# ProPrj_PocketEPD_2025-11-28.net
KiCad netlist of a schematic drawn in EasyEDA Pro
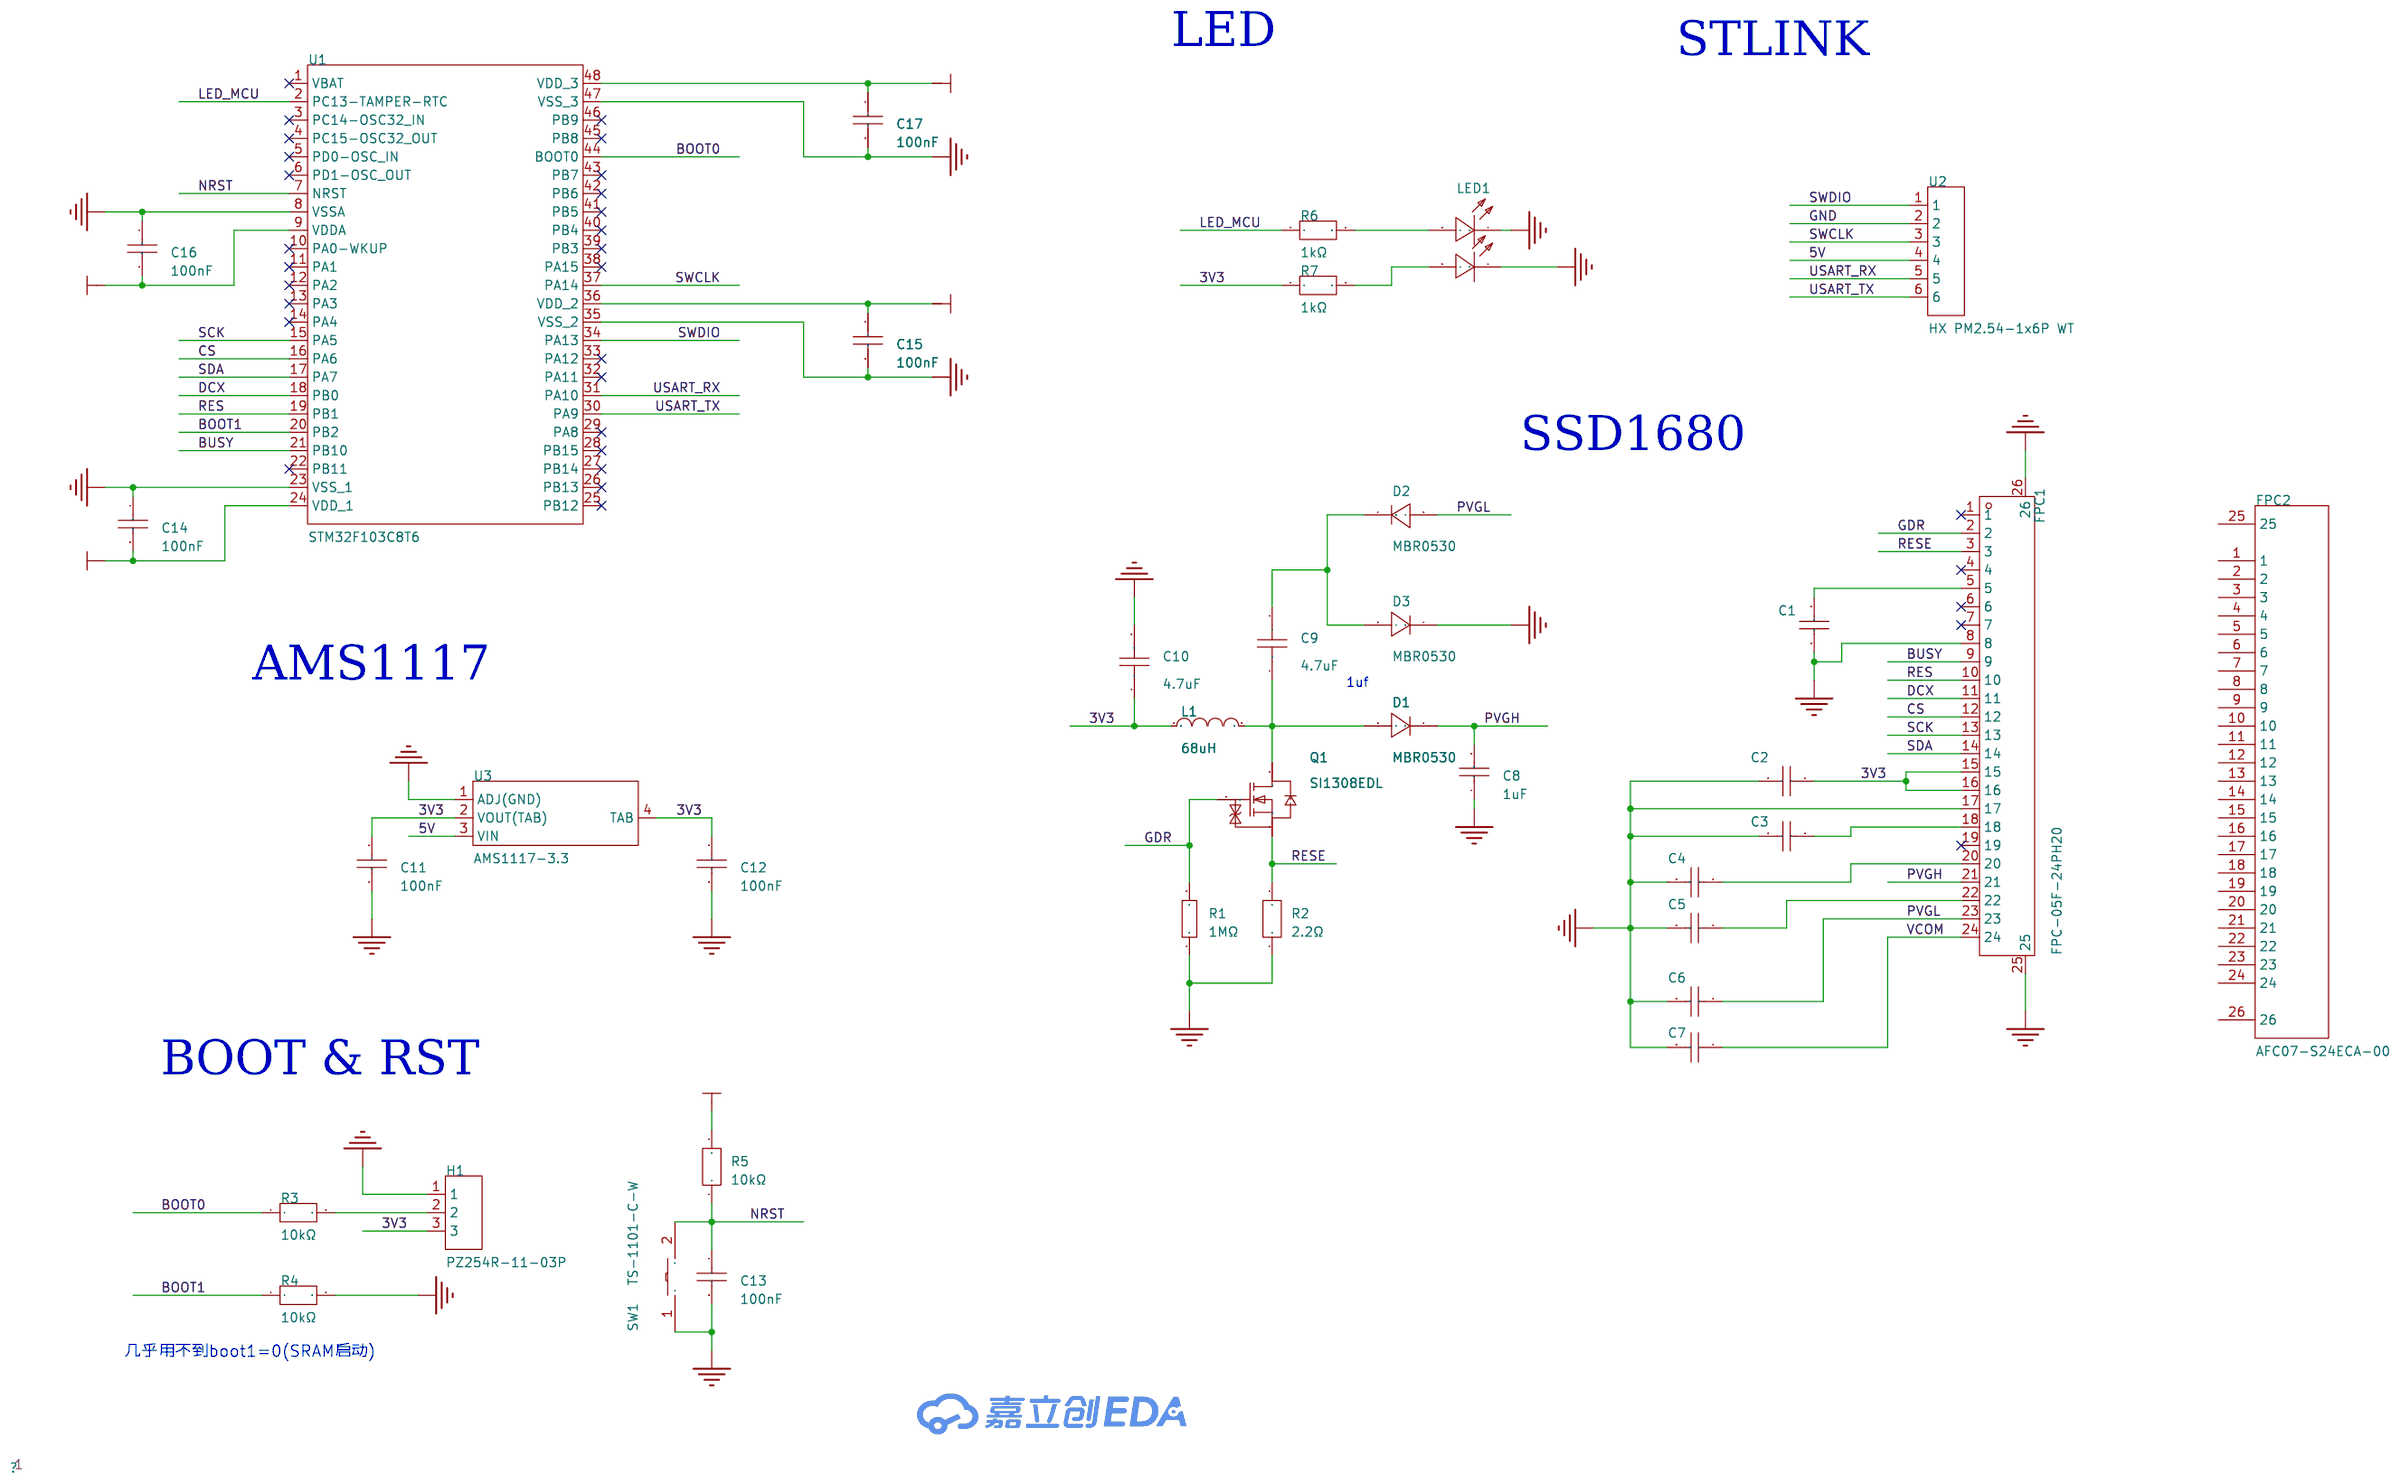
[diagram p0: schematic sheet]

(export (version "E")
  (design (tool "Eeschema 10.0.6"))
  (components
    (comp (ref "C1")
      (value "1uF")
      (footprint "easyedapro:C1206")
      (description "容值:1uF;精度:±10%;额定电压:25V;温度系数:X7R;")
      (fields
        (field (name "Manufacturer Part") "CL31B105KAHNNNE")
        (field (name "Manufacturer") "SAMSUNG(三星)")
      )
      (libsource (lib "easyedapro") (part "CL31B105KAHNNNE"))
    )
    (comp (ref "C2")
      (value "1uF")
      (footprint "easyedapro:C1206")
      (description "容值:1uF;精度:±10%;额定电压:25V;温度系数:X7R;")
      (fields
        (field (name "Manufacturer Part") "CL31B105KAHNNNE")
        (field (name "Manufacturer") "SAMSUNG(三星)")
      )
      (libsource (lib "easyedapro") (part "CL31B105KAHNNNE"))
    )
    (comp (ref "C3")
      (value "1uF")
      (footprint "easyedapro:C1206")
      (description "容值:1uF;精度:±10%;额定电压:25V;温度系数:X7R;")
      (fields
        (field (name "Manufacturer Part") "CL31B105KAHNNNE")
        (field (name "Manufacturer") "SAMSUNG(三星)")
      )
      (libsource (lib "easyedapro") (part "CL31B105KAHNNNE"))
    )
    (comp (ref "C4")
      (value "1uF")
      (footprint "easyedapro:C1206")
      (description "容值:1uF;精度:±10%;额定电压:25V;温度系数:X7R;")
      (fields
        (field (name "Manufacturer Part") "CL31B105KAHNNNE")
        (field (name "Manufacturer") "SAMSUNG(三星)")
      )
      (libsource (lib "easyedapro") (part "CL31B105KAHNNNE"))
    )
    (comp (ref "C5")
      (value "1uF")
      (footprint "easyedapro:C1206")
      (description "容值:1uF;精度:±10%;额定电压:25V;温度系数:X7R;")
      (fields
        (field (name "Manufacturer Part") "CL31B105KAHNNNE")
        (field (name "Manufacturer") "SAMSUNG(三星)")
      )
      (libsource (lib "easyedapro") (part "CL31B105KAHNNNE"))
    )
    (comp (ref "C6")
      (value "1uF")
      (footprint "easyedapro:C1206")
      (description "容值:1uF;精度:±10%;额定电压:25V;温度系数:X7R;")
      (fields
        (field (name "Manufacturer Part") "CL31B105KAHNNNE")
        (field (name "Manufacturer") "SAMSUNG(三星)")
      )
      (libsource (lib "easyedapro") (part "CL31B105KAHNNNE"))
    )
    (comp (ref "C7")
      (value "1uF")
      (footprint "easyedapro:C1206")
      (description "容值:1uF;精度:±10%;额定电压:25V;温度系数:X7R;")
      (fields
        (field (name "Manufacturer Part") "CL31B105KAHNNNE")
        (field (name "Manufacturer") "SAMSUNG(三星)")
      )
      (libsource (lib "easyedapro") (part "CL31B105KAHNNNE"))
    )
    (comp (ref "C8")
      (value "1uF")
      (footprint "easyedapro:C1206")
      (description "容值:1uF;精度:±10%;额定电压:25V;温度系数:X7R;")
      (fields
        (field (name "Manufacturer Part") "CL31B105KAHNNNE")
        (field (name "Manufacturer") "SAMSUNG(三星)")
      )
      (libsource (lib "easyedapro") (part "CL31B105KAHNNNE"))
    )
    (comp (ref "C9")
      (value "4.7uF")
      (footprint "easyedapro:C1206")
      (description "容值:4.7uF;精度:±10%;额定电压:25V;温度系数:X7R;")
      (fields (field (name "Manufacturer Part") "1206B475K250NT") (field (name "Manufacturer") "FH(风华)"))
      (libsource (lib "easyedapro") (part "1206B475K250NT"))
    )
    (comp (ref "C10")
      (value "4.7uF")
      (footprint "easyedapro:C1206")
      (description "容值:4.7uF;精度:±10%;额定电压:25V;温度系数:X7R;")
      (fields (field (name "Manufacturer Part") "1206B475K250NT") (field (name "Manufacturer") "FH(风华)"))
      (libsource (lib "easyedapro") (part "1206B475K250NT"))
    )
    (comp (ref "C11")
      (value "100nF")
      (footprint "easyedapro:C1206")
      (description "容值:100nF;精度:±10%;额定电压:100V;温度系数:X7R;")
      (fields
        (field (name "Manufacturer Part") "CL31B104KCFNNNE")
        (field (name "Manufacturer") "SAMSUNG(三星)")
      )
      (libsource (lib "easyedapro") (part "CL31B104KCFNNNE"))
    )
    (comp (ref "C12")
      (value "100nF")
      (footprint "easyedapro:C1206")
      (description "容值:100nF;精度:±10%;额定电压:100V;温度系数:X7R;")
      (fields
        (field (name "Manufacturer Part") "CL31B104KCFNNNE")
        (field (name "Manufacturer") "SAMSUNG(三星)")
      )
      (libsource (lib "easyedapro") (part "CL31B104KCFNNNE"))
    )
    (comp (ref "C13")
      (value "100nF")
      (footprint "easyedapro:C1206")
      (description "容值:100nF;精度:±10%;额定电压:100V;温度系数:X7R;")
      (fields
        (field (name "Manufacturer Part") "CL31B104KCFNNNE")
        (field (name "Manufacturer") "SAMSUNG(三星)")
      )
      (libsource (lib "easyedapro") (part "CL31B104KCFNNNE"))
    )
    (comp (ref "C14")
      (value "100nF")
      (footprint "easyedapro:C1206")
      (description "容值:100nF;精度:±10%;额定电压:100V;温度系数:X7R;")
      (fields
        (field (name "Manufacturer Part") "CL31B104KCFNNNE")
        (field (name "Manufacturer") "SAMSUNG(三星)")
      )
      (libsource (lib "easyedapro") (part "CL31B104KCFNNNE"))
    )
    (comp (ref "C15")
      (value "100nF")
      (footprint "easyedapro:C1206")
      (description "容值:100nF;精度:±10%;额定电压:100V;温度系数:X7R;")
      (fields
        (field (name "Manufacturer Part") "CL31B104KCFNNNE")
        (field (name "Manufacturer") "SAMSUNG(三星)")
      )
      (libsource (lib "easyedapro") (part "CL31B104KCFNNNE"))
    )
    (comp (ref "C16")
      (value "100nF")
      (footprint "easyedapro:C1206")
      (description "容值:100nF;精度:±10%;额定电压:100V;温度系数:X7R;")
      (fields
        (field (name "Manufacturer Part") "CL31B104KCFNNNE")
        (field (name "Manufacturer") "SAMSUNG(三星)")
      )
      (libsource (lib "easyedapro") (part "CL31B104KCFNNNE"))
    )
    (comp (ref "C17")
      (value "100nF")
      (footprint "easyedapro:C1206")
      (description "容值:100nF;精度:±10%;额定电压:100V;温度系数:X7R;")
      (fields
        (field (name "Manufacturer Part") "CL31B104KCFNNNE")
        (field (name "Manufacturer") "SAMSUNG(三星)")
      )
      (libsource (lib "easyedapro") (part "CL31B104KCFNNNE"))
    )
    (comp (ref "D1")
      (value "MBR0530")
      (footprint "easyedapro:SOD-123_L2.8-W1.8-LS3.7-RD")
      (description "二极管配置:-;正向压降(Vf):550mV@500mA;直流反向耐压(Vr):30V;整流电流:500mA;")
      (fields (field (name "Manufacturer") "CJ(江苏长电/长晶)"))
      (libsource (lib "easyedapro") (part "MBR0530"))
    )
    (comp (ref "D2")
      (value "MBR0530")
      (footprint "easyedapro:SOD-123_L2.8-W1.8-LS3.7-RD")
      (description "二极管配置:-;正向压降(Vf):550mV@500mA;直流反向耐压(Vr):30V;整流电流:500mA;")
      (fields (field (name "Manufacturer") "CJ(江苏长电/长晶)"))
      (libsource (lib "easyedapro") (part "MBR0530"))
    )
    (comp (ref "D3")
      (value "MBR0530")
      (footprint "easyedapro:SOD-123_L2.8-W1.8-LS3.7-RD")
      (description "二极管配置:-;正向压降(Vf):550mV@500mA;直流反向耐压(Vr):30V;整流电流:500mA;")
      (fields (field (name "Manufacturer") "CJ(江苏长电/长晶)"))
      (libsource (lib "easyedapro") (part "MBR0530"))
    )
    (comp (ref "FPC1")
      (value "FPC-05F-24PH20")
      (footprint "easyedapro:FPC-SMD_24P-P0.50_FPC-05F-24PH20")
      (description "锁定特性:翻盖式;触点类型:卧贴;触点数量:24P;间距:0.5mm;安装方式:下接;工作温度:-25°C~+85°C;")
      (fields (field (name "Manufacturer") "XUNPU(讯普)"))
      (libsource (lib "easyedapro") (part "FPC-05F-24PH20"))
    )
    (comp (ref "FPC2")
      (value "AFC07-S24ECA-00")
      (footprint "easyedapro:FPC-SMD_AFC07-S24ECA-00")
      (description "锁定特性:抽屉式;触点类型:上接;触点数量:24P;间距:0.5mm;安装类型:卧贴;")
      (fields (field (name "Manufacturer") "JS(钜硕电子)"))
      (libsource (lib "easyedapro") (part "AFC07-S24ECA-00"))
    )
    (comp (ref "H1")
      (value "PZ254R-11-03P")
      (footprint "easyedapro:HDR-TH_3P-P2.54-H-M-W10.4")
      (fields (field (name "Manufacturer") "XFCN(兴飞)"))
      (libsource (lib "easyedapro") (part "PZ254R-11-03P"))
    )
    (comp (ref "L1")
      (value "68uH")
      (footprint "easyedapro:IND-SMD_L4.0-W4.0_FNR40XXS")
      (description "电感值:68uH;精度:±20%;额定电流:500mA;饱和电流(Isat):670mA;类型:磁胶屏蔽绕线合金电感;")
      (fields (field (name "Manufacturer Part") "FNR4020S680MT") (field (name "Manufacturer") "cjiang(长江微电)"))
      (libsource (lib "easyedapro") (part "FNR4020S680MT"))
    )
    (comp (ref "LED1")
      (value "TJ-S3227SW1TCGLC2R6B-A5")
      (footprint "easyedapro:LED-SMD_4P-L3.2-W2.7_PD15-22C")
      (fields (field (name "Manufacturer") "TOGIALED(统佳)"))
      (libsource (lib "easyedapro") (part "TJ-S3227SW1TCGLC2R6B-A5"))
    )
    (comp (ref "Q1")
      (value "SI1308EDL")
      (footprint "easyedapro:SOT-323-3_L2.0-W1.3-P1.30-LS2.1-BR")
      (description "漏源电压(Vdss):30V;连续漏极电流(Id):1.4A;导通电阻(RDS(on)):150mΩ@4.5V,0.5A;耗散功率(Pd):360mW;阈值电压(Vgs(th)):1.5V;")
      (fields (field (name "Manufacturer") "TECH PUBLIC(台舟)"))
      (libsource (lib "easyedapro") (part "SI1308EDL_C7603347"))
    )
    (comp (ref "R1")
      (value "1MΩ")
      (footprint "easyedapro:R1206")
      (description "电阻类型:厚膜电阻;阻值:1MΩ;精度:±5%;功率:250mW;工作电压:200V;温度系数:±100ppm/°C;")
      (fields (field (name "Manufacturer Part") "FRC1206J105 TS") (field (name "Manufacturer") "FOJAN(富捷)"))
      (libsource (lib "easyedapro") (part "FRC1206J105 TS"))
    )
    (comp (ref "R2")
      (value "2.2Ω")
      (footprint "easyedapro:R1206")
      (description "电阻类型:厚膜电阻;阻值:2.2Ω;精度:±5%;功率:250mW;工作电压:200V;温度系数:±200ppm/°C;")
      (fields (field (name "Manufacturer Part") "FRC1206J2R2 TS") (field (name "Manufacturer") "FOJAN(富捷)"))
      (libsource (lib "easyedapro") (part "FRC1206J2R2 TS"))
    )
    (comp (ref "R3")
      (value "10kΩ")
      (footprint "easyedapro:R1206")
      (description "电阻类型:厚膜电阻;阻值:10kΩ;精度:±5%;功率:250mW;工作电压:200V;温度系数:±100ppm/°C;")
      (fields (field (name "Manufacturer Part") "FRC1206J103 TS") (field (name "Manufacturer") "FOJAN(富捷)"))
      (libsource (lib "easyedapro") (part "FRC1206J103 TS"))
    )
    (comp (ref "R4")
      (value "10kΩ")
      (footprint "easyedapro:R1206")
      (description "电阻类型:厚膜电阻;阻值:10kΩ;精度:±5%;功率:250mW;工作电压:200V;温度系数:±100ppm/°C;")
      (fields (field (name "Manufacturer Part") "FRC1206J103 TS") (field (name "Manufacturer") "FOJAN(富捷)"))
      (libsource (lib "easyedapro") (part "FRC1206J103 TS"))
    )
    (comp (ref "R5")
      (value "10kΩ")
      (footprint "easyedapro:R1206")
      (description "电阻类型:厚膜电阻;阻值:10kΩ;精度:±5%;功率:250mW;工作电压:200V;温度系数:±100ppm/°C;")
      (fields (field (name "Manufacturer Part") "FRC1206J103 TS") (field (name "Manufacturer") "FOJAN(富捷)"))
      (libsource (lib "easyedapro") (part "FRC1206J103 TS"))
    )
    (comp (ref "R6")
      (value "1kΩ")
      (footprint "easyedapro:R1206")
      (description "电阻类型:厚膜电阻;阻值:1kΩ;精度:±5%;功率:250mW;工作电压:200V;温度系数:±100ppm/°C;")
      (fields (field (name "Manufacturer Part") "FRC1206J102 TS") (field (name "Manufacturer") "FOJAN(富捷)"))
      (libsource (lib "easyedapro") (part "FRC1206J102 TS"))
    )
    (comp (ref "R7")
      (value "1kΩ")
      (footprint "easyedapro:R1206")
      (description "电阻类型:厚膜电阻;阻值:1kΩ;精度:±5%;功率:250mW;工作电压:200V;温度系数:±100ppm/°C;")
      (fields (field (name "Manufacturer Part") "FRC1206J102 TS") (field (name "Manufacturer") "FOJAN(富捷)"))
      (libsource (lib "easyedapro") (part "FRC1206J102 TS"))
    )
    (comp (ref "SW1")
      (value "TS-1101-C-W")
      (footprint "easyedapro:SW-SMD_L6.0-W3.3-LS8.0")
      (fields (field (name "Manufacturer") "XKB Connectivity(中国星坤)"))
      (libsource (lib "easyedapro") (part "TS-1101-C-W"))
    )
    (comp (ref "U1")
      (value "STM32F103C8T6")
      (footprint "easyedapro:LQFP-48_L7.0-W7.0-P0.50-LS9.0-BL")
      (description "CPU内核:ARM-M3;CPU最大主频:72MHz;应用领域:-;")
      (fields (field (name "Manufacturer") "ST(意法半导体)"))
      (libsource (lib "easyedapro") (part "STM32F103C8T6"))
    )
    (comp (ref "U2")
      (value "HX PM2.54-1x6P WT")
      (footprint "easyedapro:HDR-SMD_6P-P2.54-H-F-L11.5")
      (description "插孔结构:1x6P;间距:2.54mm;圆孔/方孔:方孔;安装方式:卧贴;排数:单排;总孔位数:6P;额定电流:3A;插孔方向:侧面;塑高:8.5mm;工作温度:-40°C~+105°C;")
      (fields (field (name "Manufacturer") "hanxia(韩下)"))
      (libsource (lib "easyedapro") (part "X6511FRS-06-C85D30"))
    )
    (comp (ref "U3")
      (value "AMS1117-3.3")
      (footprint "easyedapro:SOT-223-4_L6.5-W3.5-P2.30-LS7.0-BR")
      (description "输出类型:固定;工作电压:12V;输出电压:3.3V;输出电流:1A;电源纹波抑制比(PSRR):60dB@(120Hz);输出极性:正极;")
      (fields (field (name "Manufacturer") "UMW(友台半导体)"))
      (libsource (lib "easyedapro") (part "AMS1117-3.3_C347222"))
    )
  )
  (nets
    (net (code "1") (name "/5V") (class "Default")
      (node (ref "U2") (pin "4") (pinfunction "4_4") (pintype "unspecified"))
      (node (ref "U3") (pin "3") (pinfunction "VIN_3") (pintype "unspecified"))
    )
    (net (code "2") (name "/BOOT0") (class "Default")
      (node (ref "R3") (pin "1") (pinfunction "1_1") (pintype "unspecified"))
      (node (ref "U1") (pin "44") (pinfunction "BOOT0_44") (pintype "unspecified"))
    )
    (net (code "3") (name "/BOOT1") (class "Default")
      (node (ref "R4") (pin "1") (pinfunction "1_1") (pintype "unspecified"))
      (node (ref "U1") (pin "20") (pinfunction "PB2_20") (pintype "unspecified"))
    )
    (net (code "4") (name "/BUSY") (class "Default")
      (node (ref "FPC1") (pin "9") (pinfunction "9_9") (pintype "unspecified"))
      (node (ref "U1") (pin "21") (pinfunction "PB10_21") (pintype "unspecified"))
    )
    (net (code "5") (name "/CS") (class "Default")
      (node (ref "FPC1") (pin "12") (pinfunction "12_12") (pintype "unspecified"))
      (node (ref "U1") (pin "16") (pinfunction "PA6_16") (pintype "unspecified"))
    )
    (net (code "6") (name "/DCX") (class "Default")
      (node (ref "FPC1") (pin "11") (pinfunction "11_11") (pintype "unspecified"))
      (node (ref "U1") (pin "18") (pinfunction "PB0_18") (pintype "unspecified"))
    )
    (net (code "7") (name "/GDR") (class "Default")
      (node (ref "FPC1") (pin "2") (pinfunction "2_2") (pintype "unspecified"))
      (node (ref "Q1") (pin "1") (pinfunction "G_1") (pintype "unspecified"))
      (node (ref "R1") (pin "2") (pinfunction "2_2") (pintype "unspecified"))
    )
    (net (code "8") (name "/LED_MCU") (class "Default")
      (node (ref "R6") (pin "1") (pinfunction "1_1") (pintype "unspecified"))
      (node (ref "U1") (pin "2") (pinfunction "PC13-TAMPER-RTC_2") (pintype "unspecified"))
    )
    (net (code "9") (name "/NRST") (class "Default")
      (node (ref "C13") (pin "1") (pinfunction "1_1") (pintype "input"))
      (node (ref "R5") (pin "1") (pinfunction "1_1") (pintype "unspecified"))
      (node (ref "SW1") (pin "2") (pinfunction "2_2") (pintype "unspecified"))
      (node (ref "U1") (pin "7") (pinfunction "NRST_7") (pintype "unspecified"))
    )
    (net (code "10") (name "/PVGH") (class "Default")
      (node (ref "C8") (pin "2") (pinfunction "2_2") (pintype "input"))
      (node (ref "D1") (pin "1") (pinfunction "C_1") (pintype "unspecified"))
      (node (ref "FPC1") (pin "21") (pinfunction "21_21") (pintype "unspecified"))
    )
    (net (code "11") (name "/PVGL") (class "Default")
      (node (ref "C6") (pin "1") (pinfunction "1_1") (pintype "input"))
      (node (ref "D2") (pin "2") (pinfunction "A_2") (pintype "unspecified"))
      (node (ref "FPC1") (pin "23") (pinfunction "23_23") (pintype "unspecified"))
    )
    (net (code "12") (name "/RES") (class "Default")
      (node (ref "FPC1") (pin "10") (pinfunction "10_10") (pintype "unspecified"))
      (node (ref "U1") (pin "19") (pinfunction "PB1_19") (pintype "unspecified"))
    )
    (net (code "13") (name "/RESE") (class "Default")
      (node (ref "FPC1") (pin "3") (pinfunction "3_3") (pintype "unspecified"))
      (node (ref "Q1") (pin "2") (pinfunction "S_2") (pintype "unspecified"))
      (node (ref "R2") (pin "2") (pinfunction "2_2") (pintype "unspecified"))
    )
    (net (code "14") (name "/SCK") (class "Default")
      (node (ref "FPC1") (pin "13") (pinfunction "13_13") (pintype "unspecified"))
      (node (ref "U1") (pin "15") (pinfunction "PA5_15") (pintype "unspecified"))
    )
    (net (code "15") (name "/SDA") (class "Default")
      (node (ref "FPC1") (pin "14") (pinfunction "14_14") (pintype "unspecified"))
      (node (ref "U1") (pin "17") (pinfunction "PA7_17") (pintype "unspecified"))
    )
    (net (code "16") (name "/SWCLK") (class "Default")
      (node (ref "U1") (pin "37") (pinfunction "PA14_37") (pintype "unspecified"))
      (node (ref "U2") (pin "3") (pinfunction "3_3") (pintype "unspecified"))
    )
    (net (code "17") (name "/SWDIO") (class "Default")
      (node (ref "U1") (pin "34") (pinfunction "PA13_34") (pintype "unspecified"))
      (node (ref "U2") (pin "1") (pinfunction "1_1") (pintype "unspecified"))
    )
    (net (code "18") (name "/USART_RX") (class "Default")
      (node (ref "U1") (pin "31") (pinfunction "PA10_31") (pintype "unspecified"))
      (node (ref "U2") (pin "5") (pinfunction "5_5") (pintype "unspecified"))
    )
    (net (code "19") (name "/USART_TX") (class "Default")
      (node (ref "U1") (pin "30") (pinfunction "PA9_30") (pintype "unspecified"))
      (node (ref "U2") (pin "6") (pinfunction "6_6") (pintype "unspecified"))
    )
    (net (code "20") (name "/VCOM") (class "Default")
      (node (ref "C7") (pin "1") (pinfunction "1_1") (pintype "input"))
      (node (ref "FPC1") (pin "24") (pinfunction "24_24") (pintype "unspecified"))
    )
    (net (code "21") (name "3V3") (class "Default")
      (node (ref "C10") (pin "1") (pinfunction "1_1") (pintype "unspecified"))
      (node (ref "C11") (pin "2") (pinfunction "2_2") (pintype "input"))
      (node (ref "C12") (pin "2") (pinfunction "2_2") (pintype "input"))
      (node (ref "C14") (pin "2") (pinfunction "2_2") (pintype "input"))
      (node (ref "C15") (pin "2") (pinfunction "2_2") (pintype "input"))
      (node (ref "C16") (pin "2") (pinfunction "2_2") (pintype "input"))
      (node (ref "C17") (pin "1") (pinfunction "1_1") (pintype "input"))
      (node (ref "C2") (pin "1") (pinfunction "1_1") (pintype "input"))
      (node (ref "FPC1") (pin "15") (pinfunction "15_15") (pintype "unspecified"))
      (node (ref "FPC1") (pin "16") (pinfunction "16_16") (pintype "unspecified"))
      (node (ref "H1") (pin "3") (pinfunction "3_3") (pintype "unspecified"))
      (node (ref "L1") (pin "1") (pinfunction "1_1") (pintype "unspecified"))
      (node (ref "R5") (pin "2") (pinfunction "2_2") (pintype "unspecified"))
      (node (ref "R7") (pin "1") (pinfunction "1_1") (pintype "unspecified"))
      (node (ref "U1") (pin "24") (pinfunction "VDD_1_24") (pintype "unspecified"))
      (node (ref "U1") (pin "36") (pinfunction "VDD_2_36") (pintype "unspecified"))
      (node (ref "U1") (pin "48") (pinfunction "VDD_3_48") (pintype "unspecified"))
      (node (ref "U1") (pin "9") (pinfunction "VDDA_9") (pintype "unspecified"))
      (node (ref "U3") (pin "2") (pinfunction "VOUT(TAB)_2") (pintype "unspecified"))
      (node (ref "U3") (pin "4") (pinfunction "TAB_4") (pintype "unspecified"))
    )
    (net (code "22") (name "GND") (class "Default")
      (node (ref "C1") (pin "1") (pinfunction "1_1") (pintype "input"))
      (node (ref "C10") (pin "2") (pinfunction "2_2") (pintype "unspecified"))
      (node (ref "C11") (pin "1") (pinfunction "1_1") (pintype "input"))
      (node (ref "C12") (pin "1") (pinfunction "1_1") (pintype "input"))
      (node (ref "C13") (pin "2") (pinfunction "2_2") (pintype "input"))
      (node (ref "C14") (pin "1") (pinfunction "1_1") (pintype "input"))
      (node (ref "C15") (pin "1") (pinfunction "1_1") (pintype "input"))
      (node (ref "C16") (pin "1") (pinfunction "1_1") (pintype "input"))
      (node (ref "C17") (pin "2") (pinfunction "2_2") (pintype "input"))
      (node (ref "C2") (pin "2") (pinfunction "2_2") (pintype "input"))
      (node (ref "C3") (pin "2") (pinfunction "2_2") (pintype "input"))
      (node (ref "C4") (pin "2") (pinfunction "2_2") (pintype "input"))
      (node (ref "C5") (pin "2") (pinfunction "2_2") (pintype "input"))
      (node (ref "C6") (pin "2") (pinfunction "2_2") (pintype "input"))
      (node (ref "C7") (pin "2") (pinfunction "2_2") (pintype "input"))
      (node (ref "C8") (pin "1") (pinfunction "1_1") (pintype "input"))
      (node (ref "D3") (pin "1") (pinfunction "C_1") (pintype "unspecified"))
      (node (ref "FPC1") (pin "17") (pinfunction "17_17") (pintype "unspecified"))
      (node (ref "FPC1") (pin "25") (pinfunction "25_25") (pintype "unspecified"))
      (node (ref "FPC1") (pin "26") (pinfunction "26_26") (pintype "unspecified"))
      (node (ref "FPC1") (pin "8") (pinfunction "8_8") (pintype "unspecified"))
      (node (ref "H1") (pin "1") (pinfunction "1_1") (pintype "unspecified"))
      (node (ref "LED1") (pin "1") (pinfunction "C_1") (pintype "unspecified"))
      (node (ref "LED1") (pin "4") (pinfunction "C_4") (pintype "unspecified"))
      (node (ref "R1") (pin "1") (pinfunction "1_1") (pintype "unspecified"))
      (node (ref "R2") (pin "1") (pinfunction "1_1") (pintype "unspecified"))
      (node (ref "R4") (pin "2") (pinfunction "2_2") (pintype "unspecified"))
      (node (ref "SW1") (pin "1") (pinfunction "1_1") (pintype "unspecified"))
      (node (ref "U1") (pin "23") (pinfunction "VSS_1_23") (pintype "unspecified"))
      (node (ref "U1") (pin "35") (pinfunction "VSS_2_35") (pintype "unspecified"))
      (node (ref "U1") (pin "47") (pinfunction "VSS_3_47") (pintype "unspecified"))
      (node (ref "U1") (pin "8") (pinfunction "VSSA_8") (pintype "unspecified"))
      (node (ref "U2") (pin "2") (pinfunction "2_2") (pintype "unspecified"))
      (node (ref "U3") (pin "1") (pinfunction "ADJ(GND)_1") (pintype "unspecified"))
    )
    (net (code "23") (name "Net-(C1-Pad2)") (class "Default")
      (node (ref "C1") (pin "2") (pinfunction "2_2") (pintype "input"))
      (node (ref "FPC1") (pin "5") (pinfunction "5_5") (pintype "unspecified"))
    )
    (net (code "24") (name "Net-(C3-Pad1)") (class "Default")
      (node (ref "C3") (pin "1") (pinfunction "1_1") (pintype "input"))
      (node (ref "FPC1") (pin "18") (pinfunction "18_18") (pintype "unspecified"))
    )
    (net (code "25") (name "Net-(C4-Pad1)") (class "Default")
      (node (ref "C4") (pin "1") (pinfunction "1_1") (pintype "input"))
      (node (ref "FPC1") (pin "20") (pinfunction "20_20") (pintype "unspecified"))
    )
    (net (code "26") (name "Net-(C5-Pad1)") (class "Default")
      (node (ref "C5") (pin "1") (pinfunction "1_1") (pintype "input"))
      (node (ref "FPC1") (pin "22") (pinfunction "22_22") (pintype "unspecified"))
    )
    (net (code "27") (name "Net-(D1-A)") (class "Default")
      (node (ref "C9") (pin "1") (pinfunction "1_1") (pintype "unspecified"))
      (node (ref "D1") (pin "2") (pinfunction "A_2") (pintype "unspecified"))
      (node (ref "L1") (pin "2") (pinfunction "2_2") (pintype "unspecified"))
      (node (ref "Q1") (pin "3") (pinfunction "D_3") (pintype "unspecified"))
    )
    (net (code "28") (name "Net-(D2-C)") (class "Default")
      (node (ref "C9") (pin "2") (pinfunction "2_2") (pintype "unspecified"))
      (node (ref "D2") (pin "1") (pinfunction "C_1") (pintype "unspecified"))
      (node (ref "D3") (pin "2") (pinfunction "A_2") (pintype "unspecified"))
    )
    (net (code "29") (name "Net-(H1-Pad2)") (class "Default")
      (node (ref "H1") (pin "2") (pinfunction "2_2") (pintype "unspecified"))
      (node (ref "R3") (pin "2") (pinfunction "2_2") (pintype "unspecified"))
    )
    (net (code "30") (name "Net-(LED1-A-Pad2)") (class "Default")
      (node (ref "LED1") (pin "2") (pinfunction "A_2") (pintype "unspecified"))
      (node (ref "R7") (pin "2") (pinfunction "2_2") (pintype "unspecified"))
    )
    (net (code "31") (name "Net-(LED1-A-Pad3)") (class "Default")
      (node (ref "LED1") (pin "3") (pinfunction "A_3") (pintype "unspecified"))
      (node (ref "R6") (pin "2") (pinfunction "2_2") (pintype "unspecified"))
    )
    (net (code "32") (name "unconnected-(FPC1-Pad1)") (class "Default")
      (node (ref "FPC1") (pin "1") (pinfunction "1_1") (pintype "unspecified+no_connect"))
    )
    (net (code "33") (name "unconnected-(FPC1-Pad4)") (class "Default")
      (node (ref "FPC1") (pin "4") (pinfunction "4_4") (pintype "unspecified+no_connect"))
    )
    (net (code "34") (name "unconnected-(FPC1-Pad6)") (class "Default")
      (node (ref "FPC1") (pin "6") (pinfunction "6_6") (pintype "unspecified+no_connect"))
    )
    (net (code "35") (name "unconnected-(FPC1-Pad7)") (class "Default")
      (node (ref "FPC1") (pin "7") (pinfunction "7_7") (pintype "unspecified+no_connect"))
    )
    (net (code "36") (name "unconnected-(FPC1-Pad19)") (class "Default")
      (node (ref "FPC1") (pin "19") (pinfunction "19_19") (pintype "unspecified+no_connect"))
    )
    (net (code "37") (name "unconnected-(FPC2-Pad1)") (class "Default")
      (node (ref "FPC2") (pin "1") (pinfunction "1_1") (pintype "unspecified"))
    )
    (net (code "38") (name "unconnected-(FPC2-Pad2)") (class "Default")
      (node (ref "FPC2") (pin "2") (pinfunction "2_2") (pintype "unspecified"))
    )
    (net (code "39") (name "unconnected-(FPC2-Pad3)") (class "Default")
      (node (ref "FPC2") (pin "3") (pinfunction "3_3") (pintype "unspecified"))
    )
    (net (code "40") (name "unconnected-(FPC2-Pad4)") (class "Default")
      (node (ref "FPC2") (pin "4") (pinfunction "4_4") (pintype "unspecified"))
    )
    (net (code "41") (name "unconnected-(FPC2-Pad5)") (class "Default")
      (node (ref "FPC2") (pin "5") (pinfunction "5_5") (pintype "unspecified"))
    )
    (net (code "42") (name "unconnected-(FPC2-Pad6)") (class "Default")
      (node (ref "FPC2") (pin "6") (pinfunction "6_6") (pintype "unspecified"))
    )
    (net (code "43") (name "unconnected-(FPC2-Pad7)") (class "Default")
      (node (ref "FPC2") (pin "7") (pinfunction "7_7") (pintype "unspecified"))
    )
    (net (code "44") (name "unconnected-(FPC2-Pad8)") (class "Default")
      (node (ref "FPC2") (pin "8") (pinfunction "8_8") (pintype "unspecified"))
    )
    (net (code "45") (name "unconnected-(FPC2-Pad9)") (class "Default")
      (node (ref "FPC2") (pin "9") (pinfunction "9_9") (pintype "unspecified"))
    )
    (net (code "46") (name "unconnected-(FPC2-Pad10)") (class "Default")
      (node (ref "FPC2") (pin "10") (pinfunction "10_10") (pintype "unspecified"))
    )
    (net (code "47") (name "unconnected-(FPC2-Pad11)") (class "Default")
      (node (ref "FPC2") (pin "11") (pinfunction "11_11") (pintype "unspecified"))
    )
    (net (code "48") (name "unconnected-(FPC2-Pad12)") (class "Default")
      (node (ref "FPC2") (pin "12") (pinfunction "12_12") (pintype "unspecified"))
    )
    (net (code "49") (name "unconnected-(FPC2-Pad13)") (class "Default")
      (node (ref "FPC2") (pin "13") (pinfunction "13_13") (pintype "unspecified"))
    )
    (net (code "50") (name "unconnected-(FPC2-Pad14)") (class "Default")
      (node (ref "FPC2") (pin "14") (pinfunction "14_14") (pintype "unspecified"))
    )
    (net (code "51") (name "unconnected-(FPC2-Pad15)") (class "Default")
      (node (ref "FPC2") (pin "15") (pinfunction "15_15") (pintype "unspecified"))
    )
    (net (code "52") (name "unconnected-(FPC2-Pad16)") (class "Default")
      (node (ref "FPC2") (pin "16") (pinfunction "16_16") (pintype "unspecified"))
    )
    (net (code "53") (name "unconnected-(FPC2-Pad17)") (class "Default")
      (node (ref "FPC2") (pin "17") (pinfunction "17_17") (pintype "unspecified"))
    )
    (net (code "54") (name "unconnected-(FPC2-Pad18)") (class "Default")
      (node (ref "FPC2") (pin "18") (pinfunction "18_18") (pintype "unspecified"))
    )
    (net (code "55") (name "unconnected-(FPC2-Pad19)") (class "Default")
      (node (ref "FPC2") (pin "19") (pinfunction "19_19") (pintype "unspecified"))
    )
    (net (code "56") (name "unconnected-(FPC2-Pad20)") (class "Default")
      (node (ref "FPC2") (pin "20") (pinfunction "20_20") (pintype "unspecified"))
    )
    (net (code "57") (name "unconnected-(FPC2-Pad21)") (class "Default")
      (node (ref "FPC2") (pin "21") (pinfunction "21_21") (pintype "unspecified"))
    )
    (net (code "58") (name "unconnected-(FPC2-Pad22)") (class "Default")
      (node (ref "FPC2") (pin "22") (pinfunction "22_22") (pintype "unspecified"))
    )
    (net (code "59") (name "unconnected-(FPC2-Pad23)") (class "Default")
      (node (ref "FPC2") (pin "23") (pinfunction "23_23") (pintype "unspecified"))
    )
    (net (code "60") (name "unconnected-(FPC2-Pad24)") (class "Default")
      (node (ref "FPC2") (pin "24") (pinfunction "24_24") (pintype "unspecified"))
    )
    (net (code "61") (name "unconnected-(FPC2-Pad25)") (class "Default")
      (node (ref "FPC2") (pin "25") (pinfunction "25_25") (pintype "unspecified"))
    )
    (net (code "62") (name "unconnected-(FPC2-Pad26)") (class "Default")
      (node (ref "FPC2") (pin "26") (pinfunction "26_26") (pintype "unspecified"))
    )
    (net (code "63") (name "unconnected-(U1-PA0-WKUP-Pad10)") (class "Default")
      (node (ref "U1") (pin "10") (pinfunction "PA0-WKUP_10") (pintype "unspecified+no_connect"))
    )
    (net (code "64") (name "unconnected-(U1-PA1-Pad11)") (class "Default")
      (node (ref "U1") (pin "11") (pinfunction "PA1_11") (pintype "unspecified+no_connect"))
    )
    (net (code "65") (name "unconnected-(U1-PA2-Pad12)") (class "Default")
      (node (ref "U1") (pin "12") (pinfunction "PA2_12") (pintype "unspecified+no_connect"))
    )
    (net (code "66") (name "unconnected-(U1-PA3-Pad13)") (class "Default")
      (node (ref "U1") (pin "13") (pinfunction "PA3_13") (pintype "unspecified+no_connect"))
    )
    (net (code "67") (name "unconnected-(U1-PA4-Pad14)") (class "Default")
      (node (ref "U1") (pin "14") (pinfunction "PA4_14") (pintype "unspecified+no_connect"))
    )
    (net (code "68") (name "unconnected-(U1-PA8-Pad29)") (class "Default")
      (node (ref "U1") (pin "29") (pinfunction "PA8_29") (pintype "unspecified+no_connect"))
    )
    (net (code "69") (name "unconnected-(U1-PA11-Pad32)") (class "Default")
      (node (ref "U1") (pin "32") (pinfunction "PA11_32") (pintype "unspecified+no_connect"))
    )
    (net (code "70") (name "unconnected-(U1-PA12-Pad33)") (class "Default")
      (node (ref "U1") (pin "33") (pinfunction "PA12_33") (pintype "unspecified+no_connect"))
    )
    (net (code "71") (name "unconnected-(U1-PA15-Pad38)") (class "Default")
      (node (ref "U1") (pin "38") (pinfunction "PA15_38") (pintype "unspecified+no_connect"))
    )
    (net (code "72") (name "unconnected-(U1-PB3-Pad39)") (class "Default")
      (node (ref "U1") (pin "39") (pinfunction "PB3_39") (pintype "unspecified+no_connect"))
    )
    (net (code "73") (name "unconnected-(U1-PB4-Pad40)") (class "Default")
      (node (ref "U1") (pin "40") (pinfunction "PB4_40") (pintype "unspecified+no_connect"))
    )
    (net (code "74") (name "unconnected-(U1-PB5-Pad41)") (class "Default")
      (node (ref "U1") (pin "41") (pinfunction "PB5_41") (pintype "unspecified+no_connect"))
    )
    (net (code "75") (name "unconnected-(U1-PB6-Pad42)") (class "Default")
      (node (ref "U1") (pin "42") (pinfunction "PB6_42") (pintype "unspecified+no_connect"))
    )
    (net (code "76") (name "unconnected-(U1-PB7-Pad43)") (class "Default")
      (node (ref "U1") (pin "43") (pinfunction "PB7_43") (pintype "unspecified+no_connect"))
    )
    (net (code "77") (name "unconnected-(U1-PB8-Pad45)") (class "Default")
      (node (ref "U1") (pin "45") (pinfunction "PB8_45") (pintype "unspecified+no_connect"))
    )
    (net (code "78") (name "unconnected-(U1-PB9-Pad46)") (class "Default")
      (node (ref "U1") (pin "46") (pinfunction "PB9_46") (pintype "unspecified+no_connect"))
    )
    (net (code "79") (name "unconnected-(U1-PB11-Pad22)") (class "Default")
      (node (ref "U1") (pin "22") (pinfunction "PB11_22") (pintype "unspecified+no_connect"))
    )
    (net (code "80") (name "unconnected-(U1-PB12-Pad25)") (class "Default")
      (node (ref "U1") (pin "25") (pinfunction "PB12_25") (pintype "unspecified+no_connect"))
    )
    (net (code "81") (name "unconnected-(U1-PB13-Pad26)") (class "Default")
      (node (ref "U1") (pin "26") (pinfunction "PB13_26") (pintype "unspecified+no_connect"))
    )
    (net (code "82") (name "unconnected-(U1-PB14-Pad27)") (class "Default")
      (node (ref "U1") (pin "27") (pinfunction "PB14_27") (pintype "unspecified+no_connect"))
    )
    (net (code "83") (name "unconnected-(U1-PB15-Pad28)") (class "Default")
      (node (ref "U1") (pin "28") (pinfunction "PB15_28") (pintype "unspecified+no_connect"))
    )
    (net (code "84") (name "unconnected-(U1-PC14-OSC32_IN-Pad3)") (class "Default")
      (node (ref "U1") (pin "3") (pinfunction "PC14-OSC32_IN_3") (pintype "unspecified+no_connect"))
    )
    (net (code "85") (name "unconnected-(U1-PC15-OSC32_OUT-Pad4)") (class "Default")
      (node (ref "U1") (pin "4") (pinfunction "PC15-OSC32_OUT_4") (pintype "unspecified+no_connect"))
    )
    (net (code "86") (name "unconnected-(U1-PD0-OSC_IN-Pad5)") (class "Default")
      (node (ref "U1") (pin "5") (pinfunction "PD0-OSC_IN_5") (pintype "unspecified+no_connect"))
    )
    (net (code "87") (name "unconnected-(U1-PD1-OSC_OUT-Pad6)") (class "Default")
      (node (ref "U1") (pin "6") (pinfunction "PD1-OSC_OUT_6") (pintype "unspecified+no_connect"))
    )
    (net (code "88") (name "unconnected-(U1-VBAT-Pad1)") (class "Default")
      (node (ref "U1") (pin "1") (pinfunction "VBAT_1") (pintype "unspecified+no_connect"))
    )
  )
)
